# LED.net
KiCad netlist of a schematic drawn in Altium Designer
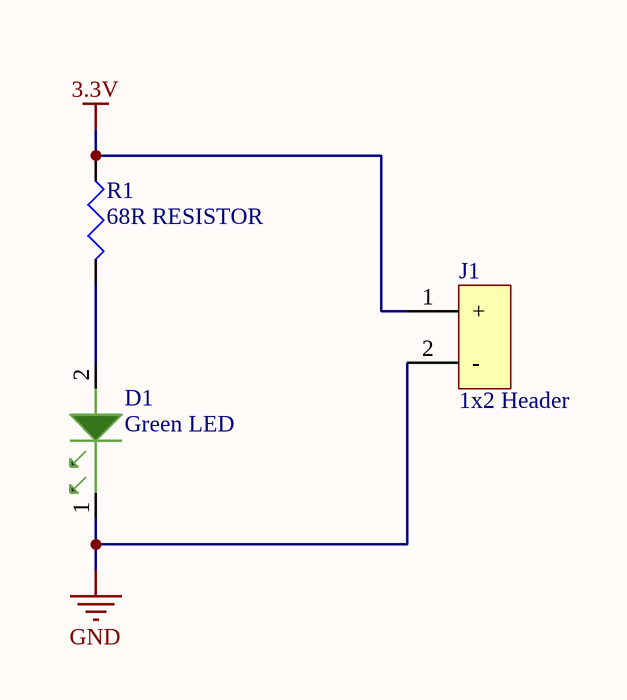
[diagram p0: LED.SchDoc]

(export (version "E")
  (design (tool "Eeschema 10.0.6"))
  (components
    (comp (ref "D1")
      (value "Green LED")
      (description "WL-SMCD SMT Mono-color Chip LED Diffused")
      (fields
        (field (name "MANUFACTURER") "Wurth Electronics")
        (field (name "MANUFACTURER PART NUMBER") "150060VS55040")
      )
      (libsource (lib "LED") (part "150060VS55040"))
    )
    (comp (ref "J1")
      (value "1x2 Header")
      (description "KK 254 Wire-to-Board Header, Vertical, with Friction Lock, 2 Circuits, Gold (Au) Plating")
      (fields (field (name "MANUFACTURER") "Molex") (field (name "MANUFACTURER PART NUMBER") "22-29-2021"))
      (libsource (lib "LED") (part "22-29-2021"))
    )
    (comp (ref "R1")
      (value "68R RESISTOR")
      (footprint "R68")
      (description "SMD Chip Resistor, 68 Ohm, ± 1%, 125 mW, 0805 [2012 Metric], Thick Film, General Purpose")
      (fields
        (field (name "MANUFACTURER") "Vishay")
        (field (name "MANUFACTURER PART NUMBER") "CRCW080568R0FKEAC")
      )
      (libsource (lib "LED") (part "CRCW080568R0FKEAC"))
    )
  )
  (nets
    (net (code "1") (name "3.3V") (class "Default")
      (node (ref "J1") (pin "1") (pinfunction "+_1") (pintype "passive"))
      (node (ref "R1") (pin "1") (pintype "passive"))
    )
    (net (code "2") (name "GND") (class "Default")
      (node (ref "D1") (pin "1") (pintype "passive"))
      (node (ref "J1") (pin "2") (pinfunction "-_2") (pintype "passive"))
    )
    (net (code "3") (name "Net-(D1-Pad2)") (class "Default")
      (node (ref "D1") (pin "2") (pintype "passive"))
      (node (ref "R1") (pin "2") (pintype "passive"))
    )
  )
)
